# RGB_Displays.net
KiCad netlist of a schematic drawn in Altium Designer
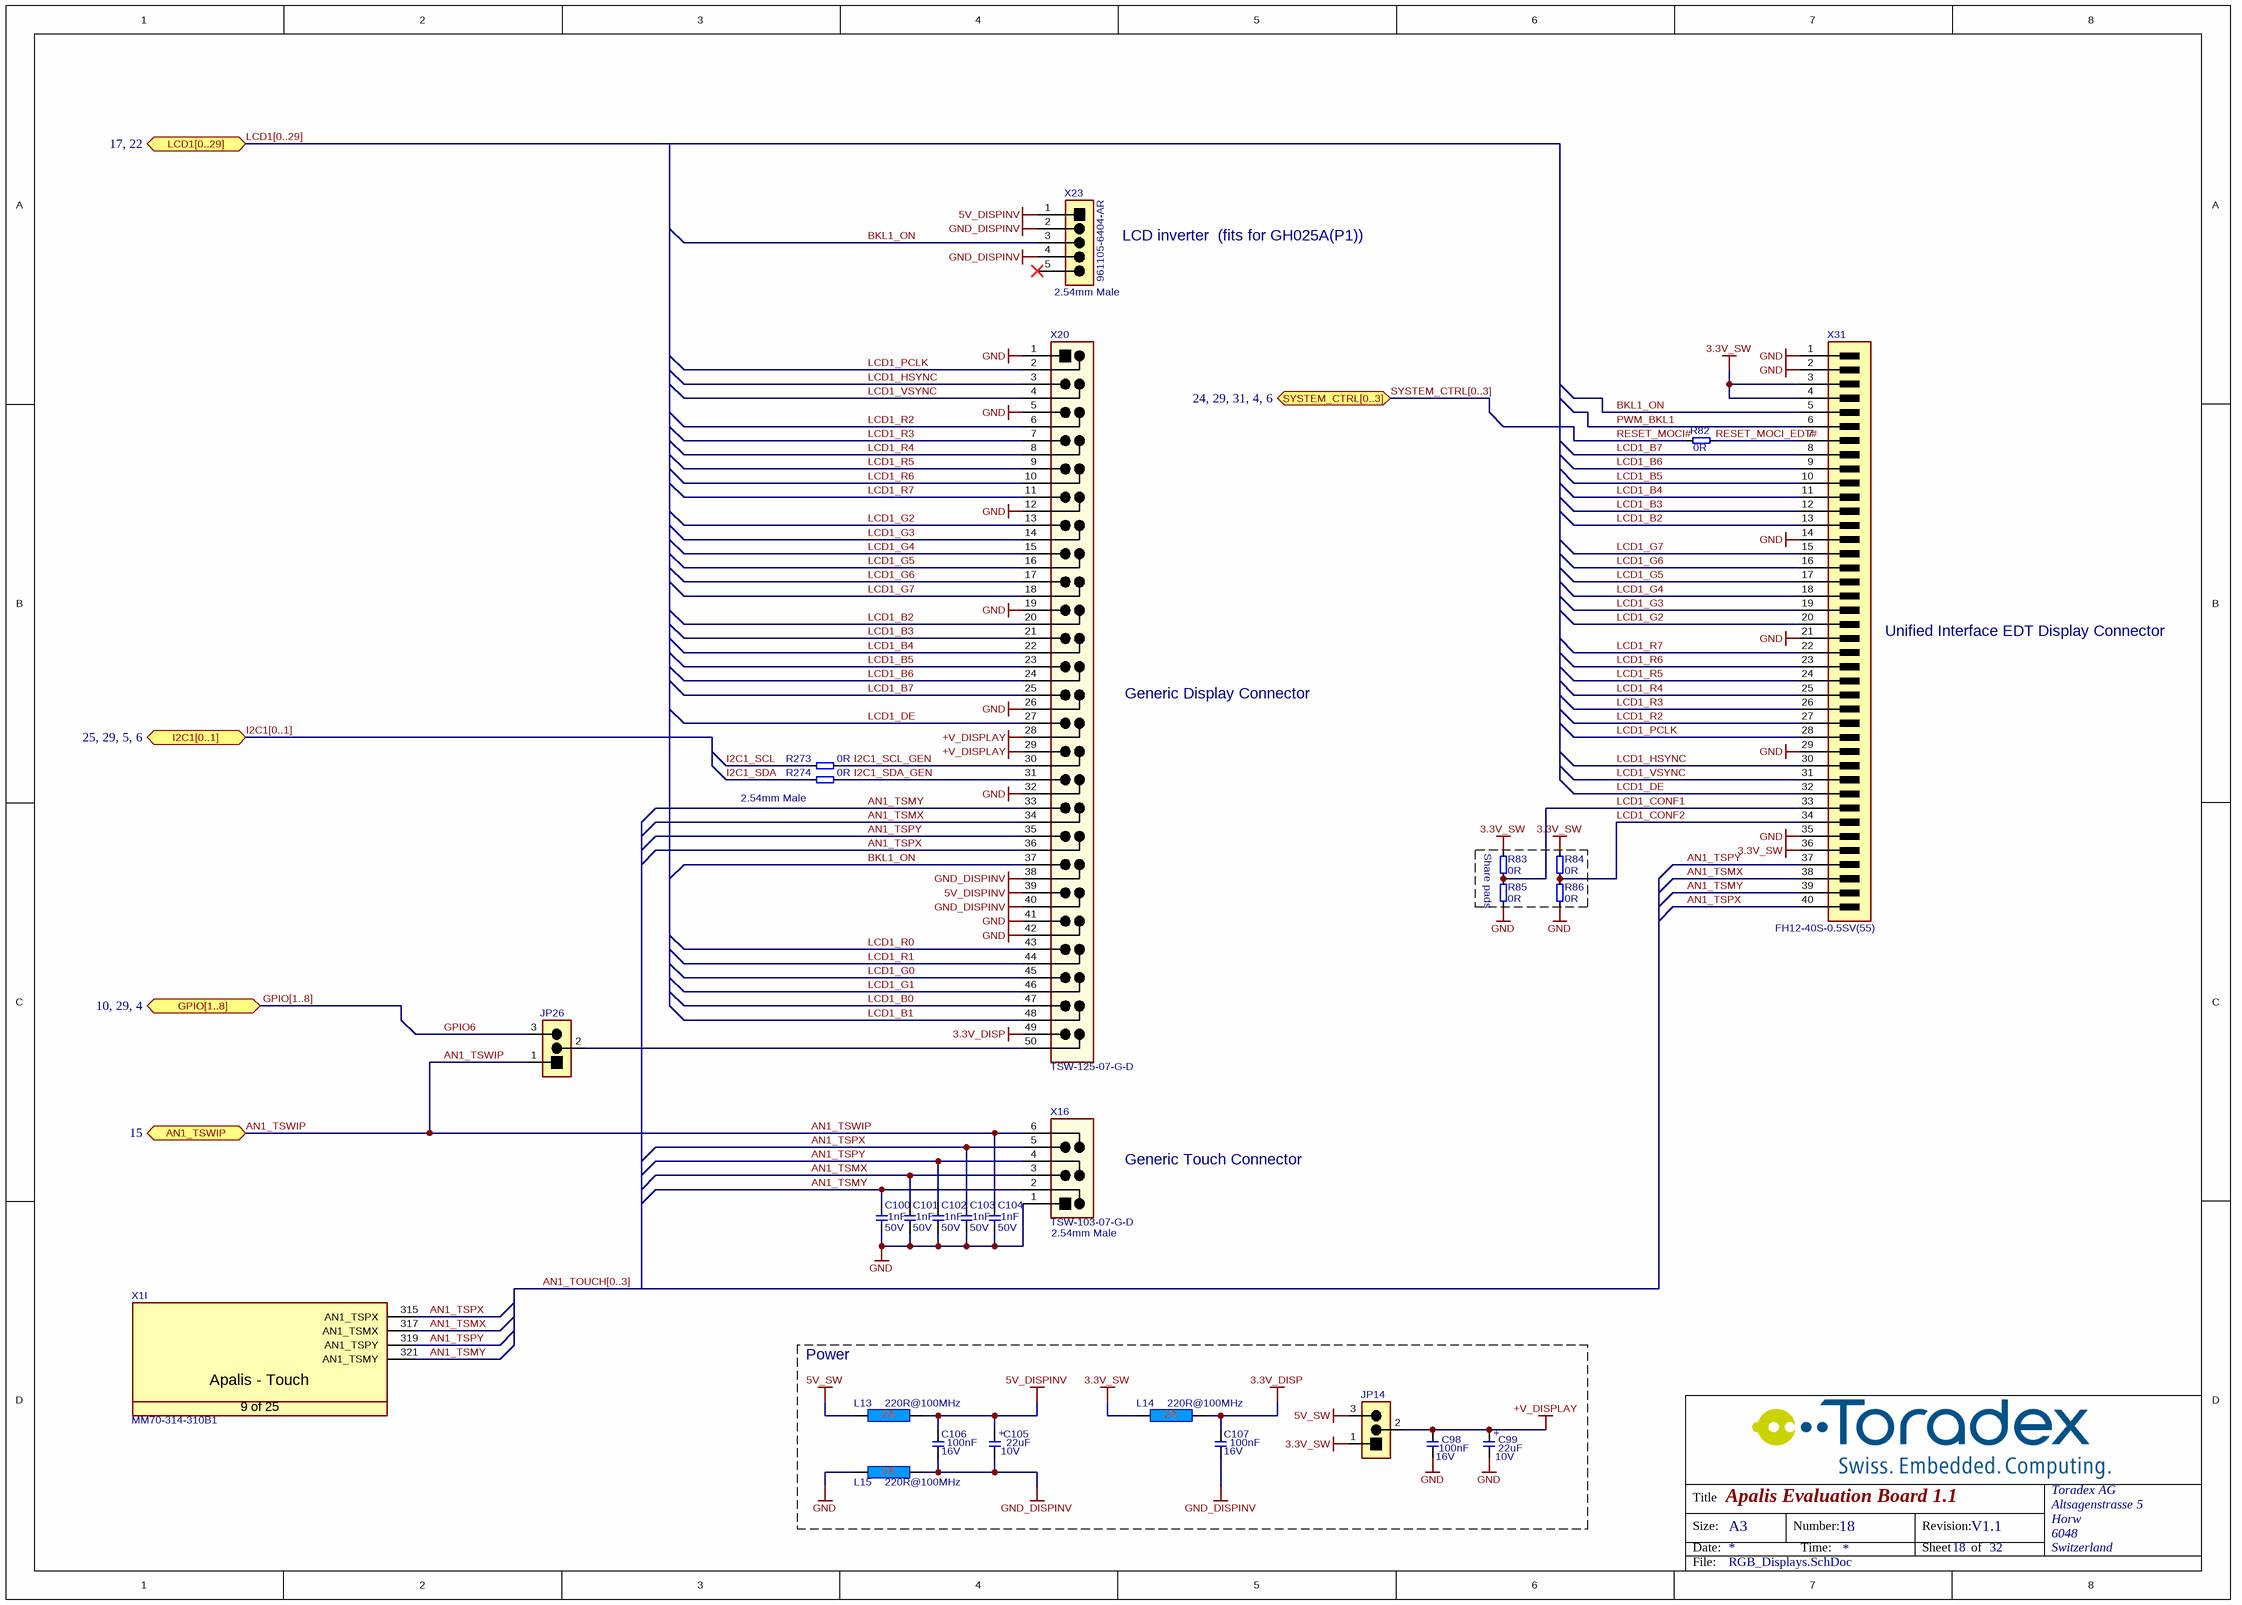
[diagram p0: RGB_Displays.SchDoc]

(export (version "E")
  (design (tool "Eeschema 10.0.6"))
  (components
    (comp (ref "C98")
      (value "100nF")
      (footprint "T_CAPC0603X33N")
      (description "Capacitor Ceramic X7R 100nF 16V 10% 0603")
      (fields (field (name "TOLERANCE") "10%") (field (name "RATING") "16V"))
      (libsource (lib "Apalis Evaluation Board") (part "C-X7R-100nF-16V-10%-0603"))
    )
    (comp (ref "C99")
      (value "22uF")
      (footprint "CAPMP3528X210N")
      (description "Capacitor TA 22uF 10V 20% 3528")
      (fields (field (name "TOLERANCE") "20%") (field (name "RATING") "10V"))
      (libsource (lib "Apalis Evaluation Board") (part "C-TA-22uF-10V-20%-3528"))
    )
    (comp (ref "C100")
      (value "1nF")
      (footprint "T_CAPC0603X33N")
      (description "Capacitor Ceramic X7R 1nF 50V 10% 0603")
      (fields (field (name "TOLERANCE") "10%") (field (name "RATING") "50V"))
      (libsource (lib "Apalis Evaluation Board") (part "C-X7R-1nF-50V-10%-0603"))
    )
    (comp (ref "C101")
      (value "1nF")
      (footprint "T_CAPC0603X33N")
      (description "Capacitor Ceramic X7R 1nF 50V 10% 0603")
      (fields (field (name "TOLERANCE") "10%") (field (name "RATING") "50V"))
      (libsource (lib "Apalis Evaluation Board") (part "C-X7R-1nF-50V-10%-0603"))
    )
    (comp (ref "C102")
      (value "1nF")
      (footprint "T_CAPC0603X33N")
      (description "Capacitor Ceramic X7R 1nF 50V 10% 0603")
      (fields (field (name "TOLERANCE") "10%") (field (name "RATING") "50V"))
      (libsource (lib "Apalis Evaluation Board") (part "C-X7R-1nF-50V-10%-0603"))
    )
    (comp (ref "C103")
      (value "1nF")
      (footprint "T_CAPC0603X33N")
      (description "Capacitor Ceramic X7R 1nF 50V 10% 0603")
      (fields (field (name "TOLERANCE") "10%") (field (name "RATING") "50V"))
      (libsource (lib "Apalis Evaluation Board") (part "C-X7R-1nF-50V-10%-0603"))
    )
    (comp (ref "C104")
      (value "1nF")
      (footprint "T_CAPC0603X33N")
      (description "Capacitor Ceramic X7R 1nF 50V 10% 0603")
      (fields (field (name "TOLERANCE") "10%") (field (name "RATING") "50V"))
      (libsource (lib "Apalis Evaluation Board") (part "C-X7R-1nF-50V-10%-0603"))
    )
    (comp (ref "C105")
      (value "22uF")
      (footprint "CAPMP3528X210N")
      (description "Capacitor TA 22uF 10V 20% 3528")
      (fields (field (name "TOLERANCE") "20%") (field (name "RATING") "10V"))
      (libsource (lib "Apalis Evaluation Board") (part "C-TA-22uF-10V-20%-3528"))
    )
    (comp (ref "C106")
      (value "100nF")
      (footprint "T_CAPC0603X33N")
      (description "Capacitor Ceramic X7R 100nF 16V 10% 0603")
      (fields (field (name "TOLERANCE") "10%") (field (name "RATING") "16V"))
      (libsource (lib "Apalis Evaluation Board") (part "C-X7R-100nF-16V-10%-0603"))
    )
    (comp (ref "C107")
      (value "100nF")
      (footprint "T_CAPC0603X33N")
      (description "Capacitor Ceramic X7R 100nF 16V 10% 0603")
      (fields (field (name "TOLERANCE") "10%") (field (name "RATING") "16V"))
      (libsource (lib "Apalis Evaluation Board") (part "C-X7R-100nF-16V-10%-0603"))
    )
    (comp (ref "JP14")
      (value "826936-3")
      (footprint "T_TYCO_826936-3")
      (description "Jumper, 3-Pin")
      (libsource (lib "Apalis Evaluation Board") (part "CON-Tyco-826936-3-1X3-2.54mm-JP"))
    )
    (comp (ref "JP26")
      (value "826936-3")
      (footprint "T_TYCO_826936-3")
      (description "Jumper, 3-Pin")
      (libsource (lib "Apalis Evaluation Board") (part "CON-Tyco-826936-3-1X3-2.54mm-JP_1"))
    )
    (comp (ref "L13")
      (value "220R@100MHz")
      (footprint "INDC1608X95N")
      (description "220R@100MHz 2A EMI FILTER")
      (fields (field (name "TOLERANCE") "25%"))
      (libsource (lib "Apalis Evaluation Board") (part "L-220R@100MHz-2A-25%-0603"))
    )
    (comp (ref "L14")
      (value "220R@100MHz")
      (footprint "INDC1608X95N")
      (description "220R@100MHz 2A EMI FILTER")
      (fields (field (name "TOLERANCE") "25%"))
      (libsource (lib "Apalis Evaluation Board") (part "L-220R@100MHz-2A-25%-0603"))
    )
    (comp (ref "L15")
      (value "220R@100MHz")
      (footprint "INDC1608X95N")
      (description "220R@100MHz 2A EMI FILTER")
      (fields (field (name "TOLERANCE") "25%"))
      (libsource (lib "Apalis Evaluation Board") (part "L-220R@100MHz-2A-25%-0603"))
    )
    (comp (ref "R82")
      (value "0R")
      (footprint "T_RESC0603X30N")
      (description "Resistor 0 ohm 63mW 1% 0603")
      (fields (field (name "TOLERANCE") "1%"))
      (libsource (lib "Apalis Evaluation Board") (part "R-0R-63mW-1%-0603"))
    )
    (comp (ref "R83")
      (value "0R")
      (footprint "T_RESC0603X30N")
      (description "Resistor 0 ohm 63mW 1% 0603")
      (fields (field (name "TOLERANCE") "1%"))
      (libsource (lib "Apalis Evaluation Board") (part "R-0R-63mW-1%-0603"))
    )
    (comp (ref "R84")
      (value "0R")
      (footprint "T_RESC0603X30N")
      (description "Resistor 0 ohm 63mW 1% 0603")
      (fields (field (name "TOLERANCE") "1%"))
      (libsource (lib "Apalis Evaluation Board") (part "R-0R-63mW-1%-0603"))
    )
    (comp (ref "R85")
      (value "0R")
      (footprint "T_RESC0603X30N")
      (description "Resistor 0 ohm 63mW 1% 0603")
      (fields (field (name "TOLERANCE") "1%"))
      (libsource (lib "Apalis Evaluation Board") (part "R-0R-63mW-1%-0603"))
    )
    (comp (ref "R86")
      (value "0R")
      (footprint "T_RESC0603X30N")
      (description "Resistor 0 ohm 63mW 1% 0603")
      (fields (field (name "TOLERANCE") "1%"))
      (libsource (lib "Apalis Evaluation Board") (part "R-0R-63mW-1%-0603"))
    )
    (comp (ref "R273")
      (value "0R")
      (footprint "T_RESC0603X30N")
      (description "Resistor 0 ohm 63mW 1% 0603")
      (fields (field (name "TOLERANCE") "1%"))
      (libsource (lib "Apalis Evaluation Board") (part "R-0R-63mW-1%-0603"))
    )
    (comp (ref "R274")
      (value "0R")
      (footprint "T_RESC0603X30N")
      (description "Resistor 0 ohm 63mW 1% 0603")
      (fields (field (name "TOLERANCE") "1%"))
      (libsource (lib "Apalis Evaluation Board") (part "R-0R-63mW-1%-0603"))
    )
    (comp (ref "X1")
      (value "CON-JAE-MM70-314-310B1-314-0.5mm")
      (footprint "T_JAE_MM70-314-310B1")
      (description "MXM3 Connector")
      (fields (field (name "MANUFACTURER PART NO.") "MM70-314-310B1"))
      (libsource (lib "Apalis Evaluation Board") (part "CON-JAE-MM70-314-310B1-314-0.5mm"))
    )
    (comp (ref "X16")
      (value "TSW-103-07-G-D")
      (footprint "T_Samtec_TSW-103-07-G-D")
      (description "Header Male, 2x3 Pins, 2.54mm pitch")
      (fields (field (name "MANUFACTURER PART NO.") "TSW-103-07-G-D"))
      (libsource (lib "Apalis Evaluation Board") (part "CON-Samtec-TSW-103-07-G-D"))
    )
    (comp (ref "X20")
      (value "TSW-125-07-G-D")
      (footprint "T_SAMTEC_TSW-125-07-G-D")
      (description "Header, 2x25 Pins, 2.54 mm pitch")
      (fields (field (name "MANUFACTURER PART NO.") "TSW-125-07-G-D"))
      (libsource (lib "Apalis Evaluation Board") (part "CON-Samtec-TSW-125-07-G-D"))
    )
    (comp (ref "X23")
      (value "961105-6404-AR")
      (footprint "T_3M_961105-6404-AR")
      (description "Audio Header 5 pins 2.54mm")
      (fields (field (name "MANUFACTURER PART NO.") "961105-6404-AR"))
      (libsource (lib "Apalis Evaluation Board") (part "CON-3M-961105-6404-AR"))
    )
    (comp (ref "X31")
      (value "FH12-40S-0.5SV(55)")
      (footprint "T_Hirose_FH12-40S-0.5SV(55)")
      (description "0.50mm Pitch FFC/FPC Vertical RGB connector")
      (fields (field (name "MANUFACTURER PART NO.") "FH12-40S-0.5SV(55)"))
      (libsource (lib "Apalis Evaluation Board") (part "CON-Hirose-FH12-40S-0.5SV(55)-0.5mm"))
    )
  )
  (nets
    (net (code "48") (name "+V_DISPLAY") (class "Default")
      (node (ref "C98") (pin "2") (pinfunction "2_2") (pintype "passive"))
      (node (ref "C99") (pin "1") (pinfunction "1_1") (pintype "passive"))
      (node (ref "JP14") (pin "2") (pinfunction "2_2") (pintype "passive"))
      (node (ref "X20") (pin "28") (pinfunction "28_28") (pintype "passive"))
      (node (ref "X20") (pin "29") (pinfunction "29_29") (pintype "passive"))
    )
    (net (code "50") (name "/AN1_TSMX") (class "Default")
      (node (ref "C101") (pin "2") (pinfunction "2_2") (pintype "passive"))
      (node (ref "X1") (pin "317") (pinfunction "AN1_TSMX_317") (pintype "passive"))
      (node (ref "X16") (pin "3") (pinfunction "3_3") (pintype "passive"))
      (node (ref "X20") (pin "34") (pinfunction "34_34") (pintype "passive"))
      (node (ref "X31") (pin "38") (pinfunction "XR_38") (pintype "passive"))
    )
    (net (code "51") (name "/AN1_TSMY") (class "Default")
      (node (ref "C100") (pin "2") (pinfunction "2_2") (pintype "passive"))
      (node (ref "X1") (pin "321") (pinfunction "AN1_TSMY_321") (pintype "passive"))
      (node (ref "X16") (pin "2") (pinfunction "2_2") (pintype "passive"))
      (node (ref "X20") (pin "33") (pinfunction "33_33") (pintype "passive"))
      (node (ref "X31") (pin "39") (pinfunction "YD_39") (pintype "passive"))
    )
    (net (code "52") (name "/AN1_TSPX") (class "Default")
      (node (ref "C103") (pin "2") (pinfunction "2_2") (pintype "passive"))
      (node (ref "X1") (pin "315") (pinfunction "AN1_TSPX_315") (pintype "passive"))
      (node (ref "X16") (pin "5") (pinfunction "5_5") (pintype "passive"))
      (node (ref "X20") (pin "36") (pinfunction "36_36") (pintype "passive"))
      (node (ref "X31") (pin "40") (pinfunction "XL_40") (pintype "passive"))
    )
    (net (code "53") (name "/AN1_TSPY") (class "Default")
      (node (ref "C102") (pin "2") (pinfunction "2_2") (pintype "passive"))
      (node (ref "X1") (pin "319") (pinfunction "AN1_TSPY_319") (pintype "passive"))
      (node (ref "X16") (pin "4") (pinfunction "4_4") (pintype "passive"))
      (node (ref "X20") (pin "35") (pinfunction "35_35") (pintype "passive"))
      (node (ref "X31") (pin "37") (pinfunction "YU_37") (pintype "passive"))
    )
    (net (code "54") (name "/AN1_TSWIP") (class "Default")
      (node (ref "C104") (pin "2") (pinfunction "2_2") (pintype "passive"))
      (node (ref "JP26") (pin "1") (pinfunction "1_1") (pintype "passive"))
      (node (ref "X16") (pin "6") (pinfunction "6_6") (pintype "passive"))
    )
    (net (code "55") (name "/BKL1_ON") (class "Default")
      (node (ref "X20") (pin "37") (pinfunction "37_37") (pintype "passive"))
      (node (ref "X23") (pin "3") (pintype "passive"))
      (node (ref "X31") (pin "5") (pinfunction "PWCTRL_5") (pintype "passive"))
    )
    (net (code "56") (name "/GPIO6") (class "Default")
      (node (ref "JP26") (pin "3") (pinfunction "3_3") (pintype "passive"))
    )
    (net (code "59") (name "/I2C1_SCL") (class "Default")
      (node (ref "R273") (pin "1") (pinfunction "1_1") (pintype "passive"))
    )
    (net (code "60") (name "/I2C1_SCL_GEN") (class "Default")
      (node (ref "R273") (pin "2") (pinfunction "2_2") (pintype "passive"))
      (node (ref "X20") (pin "30") (pinfunction "30_30") (pintype "passive"))
    )
    (net (code "61") (name "/I2C1_SDA") (class "Default")
      (node (ref "R274") (pin "1") (pinfunction "1_1") (pintype "passive"))
    )
    (net (code "62") (name "/I2C1_SDA_GEN") (class "Default")
      (node (ref "R274") (pin "2") (pinfunction "2_2") (pintype "passive"))
      (node (ref "X20") (pin "31") (pinfunction "31_31") (pintype "passive"))
    )
    (net (code "64") (name "/LCD1_B0") (class "Default")
      (node (ref "X20") (pin "47") (pinfunction "47_47") (pintype "passive"))
    )
    (net (code "65") (name "/LCD1_B1") (class "Default")
      (node (ref "X20") (pin "48") (pinfunction "48_48") (pintype "passive"))
    )
    (net (code "66") (name "/LCD1_B2") (class "Default")
      (node (ref "X20") (pin "20") (pinfunction "20_20") (pintype "passive"))
      (node (ref "X31") (pin "13") (pinfunction "B0_13") (pintype "passive"))
    )
    (net (code "67") (name "/LCD1_B3") (class "Default")
      (node (ref "X20") (pin "21") (pinfunction "21_21") (pintype "passive"))
      (node (ref "X31") (pin "12") (pinfunction "B1_12") (pintype "passive"))
    )
    (net (code "68") (name "/LCD1_B4") (class "Default")
      (node (ref "X20") (pin "22") (pinfunction "22_22") (pintype "passive"))
      (node (ref "X31") (pin "11") (pinfunction "B2_11") (pintype "passive"))
    )
    (net (code "69") (name "/LCD1_B5") (class "Default")
      (node (ref "X20") (pin "23") (pinfunction "23_23") (pintype "passive"))
      (node (ref "X31") (pin "10") (pinfunction "B3_10") (pintype "passive"))
    )
    (net (code "70") (name "/LCD1_B6") (class "Default")
      (node (ref "X20") (pin "24") (pinfunction "24_24") (pintype "passive"))
      (node (ref "X31") (pin "9") (pinfunction "B4_9") (pintype "passive"))
    )
    (net (code "71") (name "/LCD1_B7") (class "Default")
      (node (ref "X20") (pin "25") (pinfunction "25_25") (pintype "passive"))
      (node (ref "X31") (pin "8") (pinfunction "B5_8") (pintype "passive"))
    )
    (net (code "72") (name "/LCD1_CONF1") (class "Default")
      (node (ref "R83") (pin "2") (pinfunction "2_2") (pintype "passive"))
      (node (ref "R85") (pin "1") (pinfunction "1_1") (pintype "passive"))
      (node (ref "X31") (pin "33") (pinfunction "NC_33") (pintype "passive"))
    )
    (net (code "73") (name "/LCD1_CONF2") (class "Default")
      (node (ref "R84") (pin "2") (pinfunction "2_2") (pintype "passive"))
      (node (ref "R86") (pin "2") (pinfunction "2_2") (pintype "passive"))
      (node (ref "X31") (pin "34") (pinfunction "SHUT_34") (pintype "passive"))
    )
    (net (code "74") (name "/LCD1_DE") (class "Default")
      (node (ref "X20") (pin "27") (pinfunction "27_27") (pintype "passive"))
      (node (ref "X31") (pin "32") (pinfunction "ENB_32") (pintype "passive"))
    )
    (net (code "75") (name "/LCD1_G0") (class "Default")
      (node (ref "X20") (pin "45") (pinfunction "45_45") (pintype "passive"))
    )
    (net (code "76") (name "/LCD1_G1") (class "Default")
      (node (ref "X20") (pin "46") (pinfunction "46_46") (pintype "passive"))
    )
    (net (code "77") (name "/LCD1_G2") (class "Default")
      (node (ref "X20") (pin "13") (pinfunction "13_13") (pintype "passive"))
      (node (ref "X31") (pin "20") (pinfunction "G0_20") (pintype "passive"))
    )
    (net (code "78") (name "/LCD1_G3") (class "Default")
      (node (ref "X20") (pin "14") (pinfunction "14_14") (pintype "passive"))
      (node (ref "X31") (pin "19") (pinfunction "G1_19") (pintype "passive"))
    )
    (net (code "79") (name "/LCD1_G4") (class "Default")
      (node (ref "X20") (pin "15") (pinfunction "15_15") (pintype "passive"))
      (node (ref "X31") (pin "18") (pinfunction "G2_18") (pintype "passive"))
    )
    (net (code "80") (name "/LCD1_G5") (class "Default")
      (node (ref "X20") (pin "16") (pinfunction "16_16") (pintype "passive"))
      (node (ref "X31") (pin "17") (pinfunction "G3_17") (pintype "passive"))
    )
    (net (code "81") (name "/LCD1_G6") (class "Default")
      (node (ref "X20") (pin "17") (pinfunction "17_17") (pintype "passive"))
      (node (ref "X31") (pin "16") (pinfunction "G4_16") (pintype "passive"))
    )
    (net (code "82") (name "/LCD1_G7") (class "Default")
      (node (ref "X20") (pin "18") (pinfunction "18_18") (pintype "passive"))
      (node (ref "X31") (pin "15") (pinfunction "G5_15") (pintype "passive"))
    )
    (net (code "83") (name "/LCD1_HSYNC") (class "Default")
      (node (ref "X20") (pin "3") (pinfunction "3_3") (pintype "passive"))
      (node (ref "X31") (pin "30") (pinfunction "HSYNC_30") (pintype "passive"))
    )
    (net (code "84") (name "/LCD1_PCLK") (class "Default")
      (node (ref "X20") (pin "2") (pinfunction "2_2") (pintype "passive"))
      (node (ref "X31") (pin "28") (pinfunction "DCLK_28") (pintype "passive"))
    )
    (net (code "85") (name "/LCD1_R0") (class "Default")
      (node (ref "X20") (pin "43") (pinfunction "43_43") (pintype "passive"))
    )
    (net (code "86") (name "/LCD1_R1") (class "Default")
      (node (ref "X20") (pin "44") (pinfunction "44_44") (pintype "passive"))
    )
    (net (code "87") (name "/LCD1_R2") (class "Default")
      (node (ref "X20") (pin "6") (pinfunction "6_6") (pintype "passive"))
      (node (ref "X31") (pin "27") (pinfunction "R0_27") (pintype "passive"))
    )
    (net (code "88") (name "/LCD1_R3") (class "Default")
      (node (ref "X20") (pin "7") (pinfunction "7_7") (pintype "passive"))
      (node (ref "X31") (pin "26") (pinfunction "R1_26") (pintype "passive"))
    )
    (net (code "89") (name "/LCD1_R4") (class "Default")
      (node (ref "X20") (pin "8") (pinfunction "8_8") (pintype "passive"))
      (node (ref "X31") (pin "25") (pinfunction "R2_25") (pintype "passive"))
    )
    (net (code "90") (name "/LCD1_R5") (class "Default")
      (node (ref "X20") (pin "9") (pinfunction "9_9") (pintype "passive"))
      (node (ref "X31") (pin "24") (pinfunction "R3_24") (pintype "passive"))
    )
    (net (code "91") (name "/LCD1_R6") (class "Default")
      (node (ref "X20") (pin "10") (pinfunction "10_10") (pintype "passive"))
      (node (ref "X31") (pin "23") (pinfunction "R4_23") (pintype "passive"))
    )
    (net (code "92") (name "/LCD1_R7") (class "Default")
      (node (ref "X20") (pin "11") (pinfunction "11_11") (pintype "passive"))
      (node (ref "X31") (pin "22") (pinfunction "R5_22") (pintype "passive"))
    )
    (net (code "93") (name "/LCD1_VSYNC") (class "Default")
      (node (ref "X20") (pin "4") (pinfunction "4_4") (pintype "passive"))
      (node (ref "X31") (pin "31") (pinfunction "VSYNC_31") (pintype "passive"))
    )
    (net (code "94") (name "/PWM_BKL1") (class "Default")
      (node (ref "X31") (pin "6") (pinfunction "LEDCTRL_6") (pintype "passive"))
    )
    (net (code "95") (name "/RESET_MOCI#") (class "Default")
      (node (ref "R82") (pin "1") (pinfunction "1_1") (pintype "passive"))
    )
    (net (code "96") (name "/RESET_MOCI_EDT#") (class "Default")
      (node (ref "R82") (pin "2") (pinfunction "2_2") (pintype "passive"))
      (node (ref "X31") (pin "7") (pinfunction "RESET#_7") (pintype "passive"))
    )
    (net (code "98") (name "3.3V_DISP") (class "Default")
      (node (ref "C107") (pin "2") (pinfunction "2_2") (pintype "passive"))
      (node (ref "L14") (pin "2") (pinfunction "2_2") (pintype "passive"))
      (node (ref "X20") (pin "49") (pinfunction "49_49") (pintype "passive"))
    )
    (net (code "99") (name "3.3V_SW") (class "Default")
      (node (ref "JP14") (pin "1") (pinfunction "1_1") (pintype "passive"))
      (node (ref "L14") (pin "1") (pinfunction "1_1") (pintype "passive"))
      (node (ref "R83") (pin "1") (pinfunction "1_1") (pintype "passive"))
      (node (ref "R84") (pin "1") (pinfunction "1_1") (pintype "passive"))
      (node (ref "X31") (pin "3") (pinfunction "VCC_3") (pintype "power_in"))
      (node (ref "X31") (pin "36") (pinfunction "VDD_36") (pintype "passive"))
      (node (ref "X31") (pin "4") (pinfunction "VCC_4") (pintype "power_in"))
    )
    (net (code "100") (name "5V_DISPINV") (class "Default")
      (node (ref "C105") (pin "1") (pinfunction "1_1") (pintype "passive"))
      (node (ref "C106") (pin "2") (pinfunction "2_2") (pintype "passive"))
      (node (ref "L13") (pin "2") (pinfunction "2_2") (pintype "passive"))
      (node (ref "X20") (pin "39") (pinfunction "39_39") (pintype "passive"))
      (node (ref "X23") (pin "1") (pintype "passive"))
    )
    (net (code "101") (name "5V_SW") (class "Default")
      (node (ref "JP14") (pin "3") (pinfunction "3_3") (pintype "passive"))
      (node (ref "L13") (pin "1") (pinfunction "1_1") (pintype "passive"))
    )
    (net (code "102") (name "GND") (class "Default")
      (node (ref "C100") (pin "1") (pinfunction "1_1") (pintype "passive"))
      (node (ref "C101") (pin "1") (pinfunction "1_1") (pintype "passive"))
      (node (ref "C102") (pin "1") (pinfunction "1_1") (pintype "passive"))
      (node (ref "C103") (pin "1") (pinfunction "1_1") (pintype "passive"))
      (node (ref "C104") (pin "1") (pinfunction "1_1") (pintype "passive"))
      (node (ref "C98") (pin "1") (pinfunction "1_1") (pintype "passive"))
      (node (ref "C99") (pin "2") (pinfunction "2_2") (pintype "passive"))
      (node (ref "L15") (pin "1") (pinfunction "1_1") (pintype "passive"))
      (node (ref "R85") (pin "2") (pinfunction "2_2") (pintype "passive"))
      (node (ref "R86") (pin "1") (pinfunction "1_1") (pintype "passive"))
      (node (ref "X16") (pin "1") (pinfunction "1_1") (pintype "passive"))
      (node (ref "X20") (pin "1") (pinfunction "1_1") (pintype "passive"))
      (node (ref "X20") (pin "12") (pinfunction "12_12") (pintype "passive"))
      (node (ref "X20") (pin "19") (pinfunction "19_19") (pintype "passive"))
      (node (ref "X20") (pin "26") (pinfunction "26_26") (pintype "passive"))
      (node (ref "X20") (pin "32") (pinfunction "32_32") (pintype "passive"))
      (node (ref "X20") (pin "41") (pinfunction "41_41") (pintype "passive"))
      (node (ref "X20") (pin "42") (pinfunction "42_42") (pintype "passive"))
      (node (ref "X20") (pin "5") (pinfunction "5_5") (pintype "passive"))
      (node (ref "X31") (pin "1") (pinfunction "VSS_1") (pintype "power_in"))
      (node (ref "X31") (pin "14") (pinfunction "VSS_14") (pintype "passive"))
      (node (ref "X31") (pin "2") (pinfunction "VSS_2") (pintype "power_in"))
      (node (ref "X31") (pin "21") (pinfunction "VSS_21") (pintype "passive"))
      (node (ref "X31") (pin "29") (pinfunction "VSS_29") (pintype "passive"))
      (node (ref "X31") (pin "35") (pinfunction "VSS_35") (pintype "passive"))
    )
    (net (code "103") (name "GND_DISPINV") (class "Default")
      (node (ref "C105") (pin "2") (pinfunction "2_2") (pintype "passive"))
      (node (ref "C106") (pin "1") (pinfunction "1_1") (pintype "passive"))
      (node (ref "C107") (pin "1") (pinfunction "1_1") (pintype "passive"))
      (node (ref "L15") (pin "2") (pinfunction "2_2") (pintype "passive"))
      (node (ref "X20") (pin "38") (pinfunction "38_38") (pintype "passive"))
      (node (ref "X20") (pin "40") (pinfunction "40_40") (pintype "passive"))
      (node (ref "X23") (pin "2") (pintype "passive"))
      (node (ref "X23") (pin "4") (pintype "passive"))
    )
    (net (code "104") (name "Net-(JP26-Pad2)") (class "Default")
      (node (ref "JP26") (pin "2") (pinfunction "2_2") (pintype "passive"))
      (node (ref "X20") (pin "50") (pinfunction "50_50") (pintype "passive"))
    )
    (net (code "105") (name "unconnected-(X23-Pad5)") (class "Default")
      (node (ref "X23") (pin "5") (pintype "passive+no_connect"))
    )
  )
)
